# CC1101RGPR.net
KiCad netlist of a schematic drawn in Altium Designer
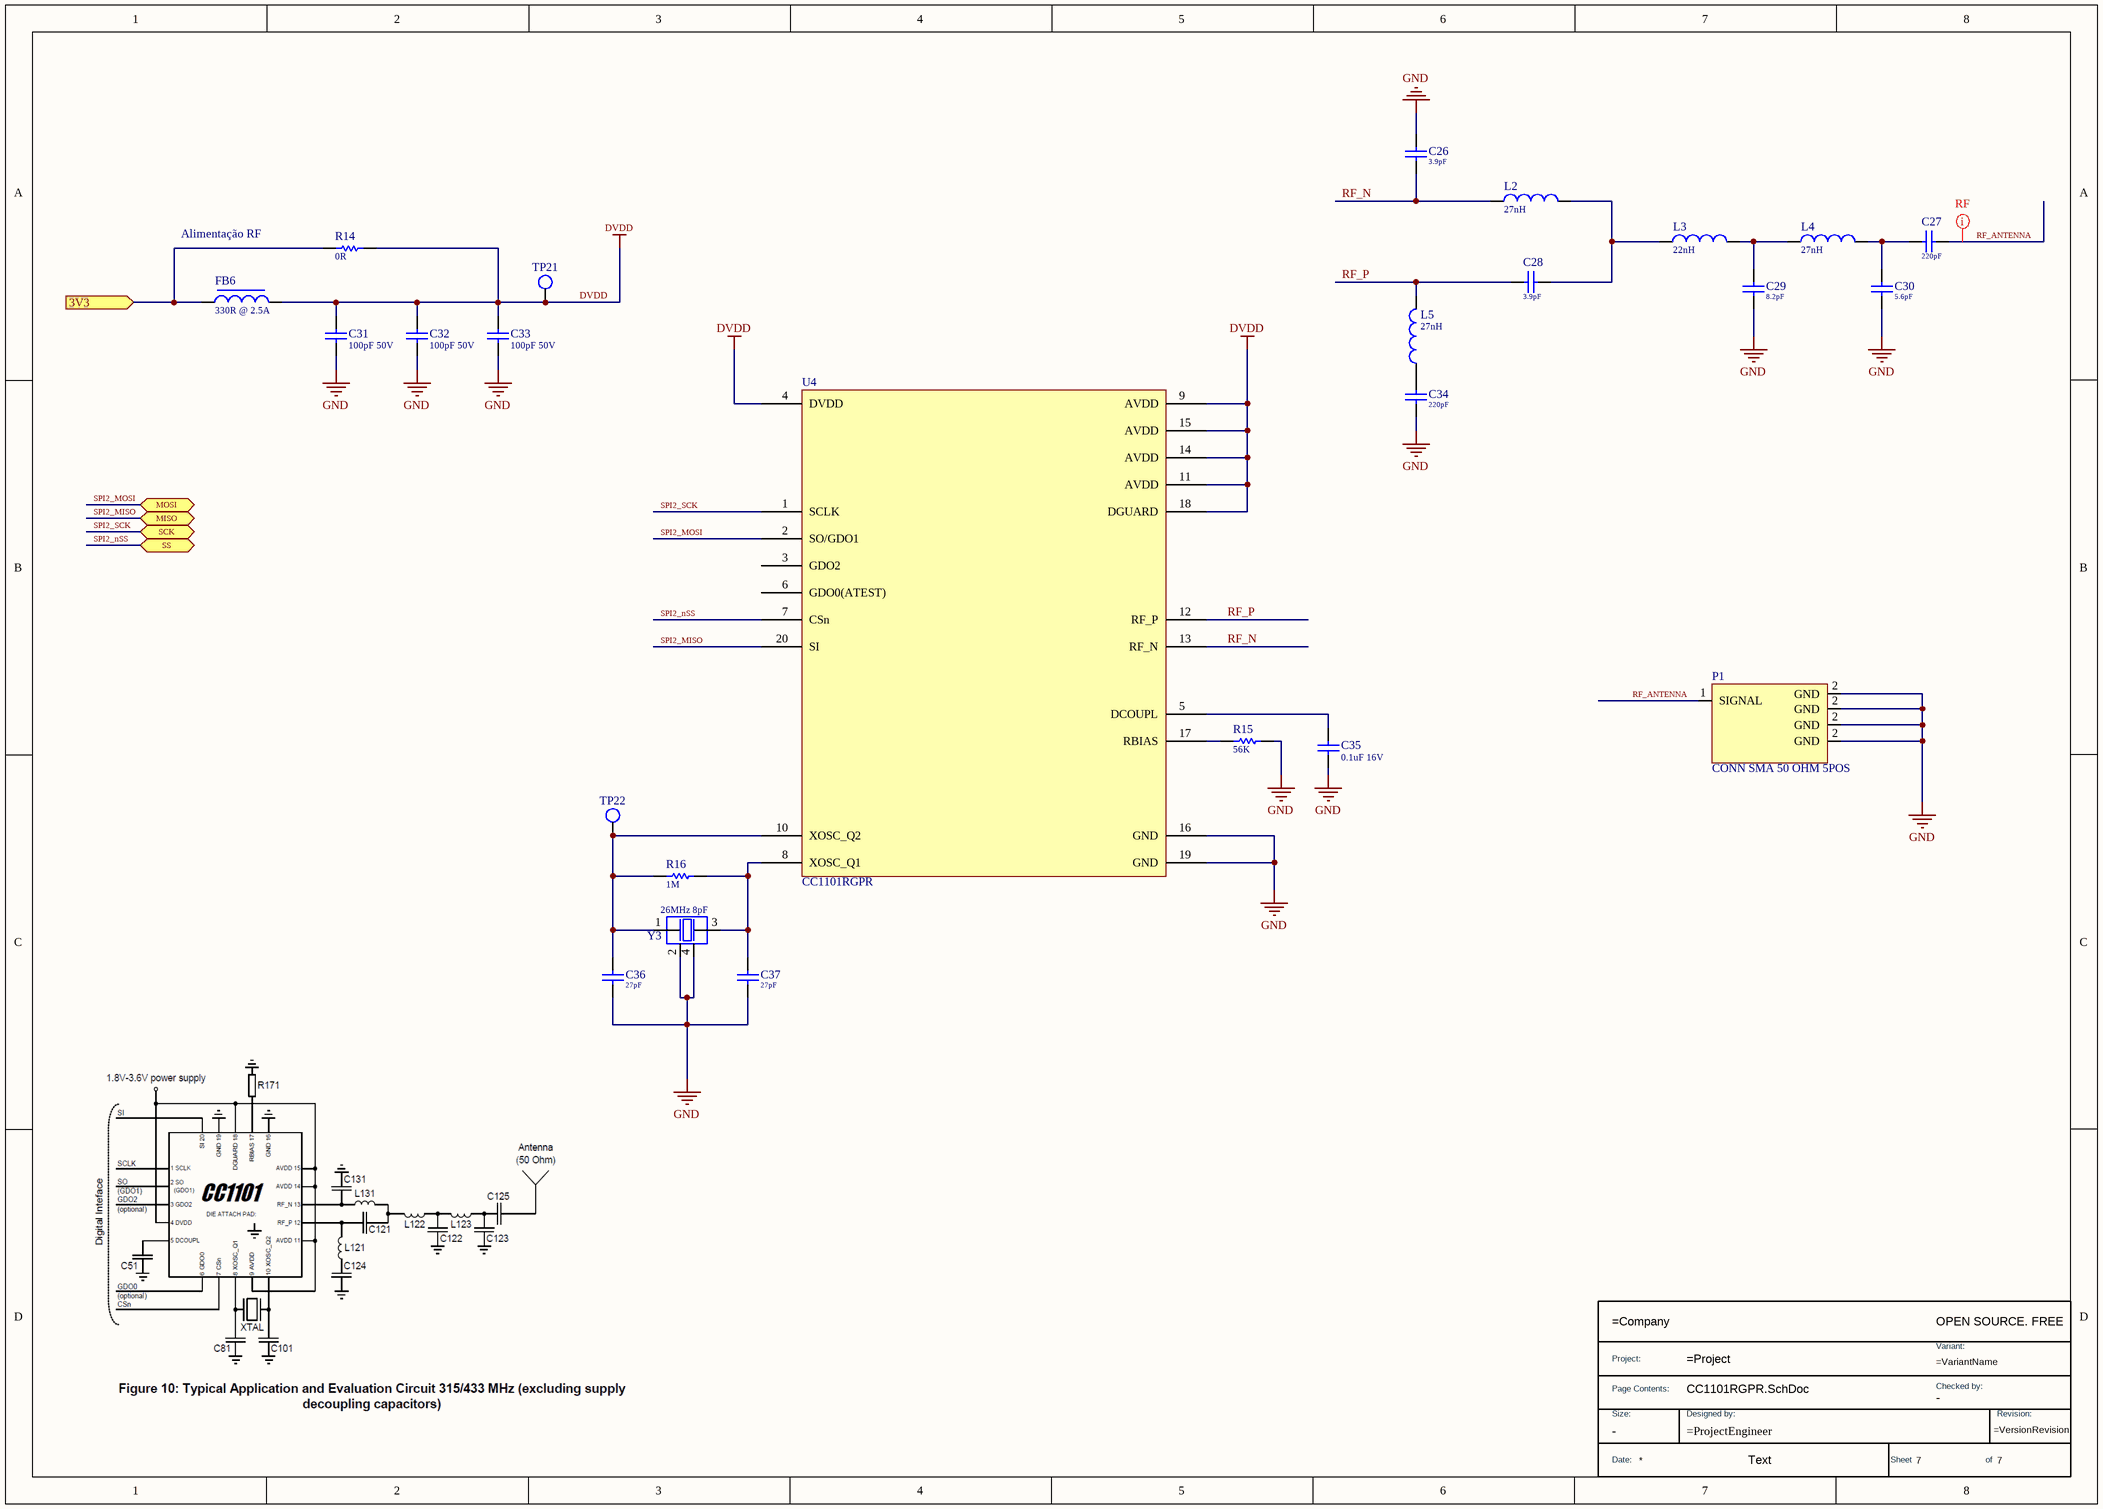
[diagram p0: CC1101RGPR.SchDoc]

(export (version "E")
  (design (tool "Eeschema 10.0.6"))
  (components
    (comp (ref "C26")
      (value "GJM1555C1H3R9WB01D")
      (footprint "CAP 0402")
      (description "CAP CER 3.9PF 50V C0G/NP0 0402")
      (fields (field (name "MANUFACTURER") "Murata Electronics") (field (name "VALOR") "3.9pF"))
      (libsource (lib "OBDH_Ed02") (part "GJM1555C1H3R9WB01D"))
    )
    (comp (ref "C27")
      (value "GRM155R71H221JA01D")
      (footprint "CAP 0402")
      (description "CAP CER 220PF 50V X7R 0402")
      (fields (field (name "MANUFACTURER") "Murata Electronics") (field (name "VALOR") "220pF"))
      (libsource (lib "OBDH_Ed02") (part "GRM155R71H221JA01D"))
    )
    (comp (ref "C28")
      (value "GJM1555C1H3R9WB01D")
      (footprint "CAP 0402")
      (description "CAP CER 3.9PF 50V C0G/NP0 0402")
      (fields (field (name "MANUFACTURER") "Murata Electronics") (field (name "VALOR") "3.9pF"))
      (libsource (lib "OBDH_Ed02") (part "GJM1555C1H3R9WB01D"))
    )
    (comp (ref "C29")
      (value "GCM1555C1H8R2CA16D")
      (footprint "CAP 0402")
      (description "CAP CER 8.2PF 50V C0G/NP0 0402")
      (fields (field (name "MANUFACTURER") "Murata Electronics") (field (name "VALOR") "8.2pF"))
      (libsource (lib "OBDH_Ed02") (part "GCM1555C1H8R2CA16D"))
    )
    (comp (ref "C30")
      (value "GRM1555C1H5R6CA01D")
      (footprint "CAP 0402")
      (description "CAP CER 5.6PF 50V C0G/NP0 0402")
      (fields (field (name "MANUFACTURER") "Murata Electronics") (field (name "VALOR") "5.6pF"))
      (libsource (lib "OBDH_Ed02") (part "GRM1555C1H5R6CA01D"))
    )
    (comp (ref "C31")
      (value "CC0805JRNPO9BN101")
      (footprint "CAP_0805")
      (description "CAP CER 100PF 50V C0G/NPO 0805")
      (fields (field (name "MANUFACTURER") "YAGEO") (field (name "VALOR") "100pF 50V"))
      (libsource (lib "OBDH_Ed02") (part "CC0805JRNPO9BN101"))
    )
    (comp (ref "C32")
      (value "CC0805JRNPO9BN101")
      (footprint "CAP_0805")
      (description "CAP CER 100PF 50V C0G/NPO 0805")
      (fields (field (name "MANUFACTURER") "YAGEO") (field (name "VALOR") "100pF 50V"))
      (libsource (lib "OBDH_Ed02") (part "CC0805JRNPO9BN101"))
    )
    (comp (ref "C33")
      (value "CC0805JRNPO9BN101")
      (footprint "CAP_0805")
      (description "CAP CER 100PF 50V C0G/NPO 0805")
      (fields (field (name "MANUFACTURER") "YAGEO") (field (name "VALOR") "100pF 50V"))
      (libsource (lib "OBDH_Ed02") (part "CC0805JRNPO9BN101"))
    )
    (comp (ref "C34")
      (value "GRM155R71H221JA01D")
      (footprint "CAP 0402")
      (description "CAP CER 220PF 50V X7R 0402")
      (fields (field (name "MANUFACTURER") "Murata Electronics") (field (name "VALOR") "220pF"))
      (libsource (lib "OBDH_Ed02") (part "GRM155R71H221JA01D"))
    )
    (comp (ref "C35")
      (value "CL05B104KO5NNNC")
      (footprint "CAP_0805")
      (description "CAP CER 0.1UF 16V X5R 0805")
      (fields (field (name "MANUFACTURER") "Samsung Electro-Mechanics") (field (name "VALOR") "0.1uF 16V"))
      (libsource (lib "OBDH_Ed02") (part "CL05B104KO5NNNC"))
    )
    (comp (ref "C36")
      (value "GCM1555C1H270JA16D")
      (footprint "CAP 0402")
      (description "CAP CER 27PF 50V C0G/NP0 0402")
      (fields (field (name "MANUFACTURER") "Murata Electronics") (field (name "VALOR") "27pF"))
      (libsource (lib "OBDH_Ed02") (part "GCM1555C1H270JA16D"))
    )
    (comp (ref "C37")
      (value "GCM1555C1H270JA16D")
      (footprint "CAP 0402")
      (description "CAP CER 27PF 50V C0G/NP0 0402")
      (fields (field (name "MANUFACTURER") "Murata Electronics") (field (name "VALOR") "27pF"))
      (libsource (lib "OBDH_Ed02") (part "GCM1555C1H270JA16D"))
    )
    (comp (ref "FB6")
      (value "MPZ2012S331AT000")
      (footprint "IND_0805")
      (description "FERRITE BEAD 330 OHM 0805 1LN")
      (fields (field (name "MANUFACTURER") "TDK Corporation") (field (name "VALOR") "330R @ 2.5A"))
      (libsource (lib "OBDH_Ed02") (part "MPZ2012S331AT000"))
    )
    (comp (ref "L2")
      (value "27nH")
      (footprint "IND 0402")
      (description "FIXED IND 27NH 350MA 460MOHM SMD")
      (fields
        (field (name "MANUFACTURER") "Murata Electronics")
        (field (name "MANUFACTURER PART NUMBER") "LQG15HS27NH02D")
      )
      (libsource (lib "OBDH_Ed02") (part "LQG15HS27NH02D"))
    )
    (comp (ref "L3")
      (value "22nH")
      (footprint "IND 0402")
      (description "FIXED IND 22NH 350MA 580MOHM SMD")
      (fields
        (field (name "MANUFACTURER") "Murata Electronics")
        (field (name "MANUFACTURER PART NUMBER") "LQG15HN22NH02D")
      )
      (libsource (lib "OBDH_Ed02") (part "LQG15HN22NH02D"))
    )
    (comp (ref "L4")
      (value "27nH")
      (footprint "IND 0402")
      (description "FIXED IND 27NH 350MA 460MOHM SMD")
      (fields
        (field (name "MANUFACTURER") "Murata Electronics")
        (field (name "MANUFACTURER PART NUMBER") "LQG15HS27NH02D")
      )
      (libsource (lib "OBDH_Ed02") (part "LQG15HS27NH02D"))
    )
    (comp (ref "L5")
      (value "27nH")
      (footprint "IND 0402")
      (description "FIXED IND 27NH 350MA 460MOHM SMD")
      (fields
        (field (name "MANUFACTURER") "Murata Electronics")
        (field (name "MANUFACTURER PART NUMBER") "LQG15HS27NH02D")
      )
      (libsource (lib "OBDH_Ed02") (part "LQG15HS27NH02D"))
    )
    (comp (ref "P1")
      (value "CONN SMA 50 OHM 5POS")
      (footprint "CONN PTH SMA JACK CONSMA002-L-G")
      (description "CONN SMA JACK R/A 50OHM PCB")
      (libsource (lib "OBDH_Ed02") (part "CONN SMA 50 OHM 5POS"))
    )
    (comp (ref "R14")
      (value "RC0805JR-070RL")
      (footprint "RES_0805")
      (description "RES 0 OHM JUMPER 1/8W 0805")
      (fields (field (name "MANUFACTURER") "YAGEO") (field (name "VALOR") "0R"))
      (libsource (lib "OBDH_Ed02") (part "RC0805JR-070RL"))
    )
    (comp (ref "R15")
      (value "**CRCW080562K0JNEA")
      (footprint "RES_0805")
      (description "RES SMD 56K OHM 5% 1/8W 0805")
      (fields
        (field (name "MANUFACTURER") "YAGEO")
        (field (name "MANUFACTURER PART NUMBER") "CRCW080562K0JNEA")
        (field (name "VALOR") "56K")
      )
      (libsource (lib "OBDH_Ed02") (part "**CRCW080562K0JNEA"))
    )
    (comp (ref "R16")
      (value "CRCW08051M00JNEA")
      (footprint "RES 0402")
      (description "RES SMD 1M OHM 5% 1/8W 0805")
      (fields (field (name "MANUFACTURER") "Vishay Intertech") (field (name "VALOR") "1M"))
      (libsource (lib "OBDH_Ed02") (part "CRCW08051M00JNEA"))
    )
    (comp (ref "TP21")
      (value "TEST_POINT_1.5MM")
      (footprint "TESTPOINT_1.5MM")
      (description "TEST_POINT")
      (libsource (lib "OBDH_Ed02") (part "TEST_POINT_1.5MM"))
    )
    (comp (ref "TP22")
      (value "TEST_POINT_1.5MM")
      (footprint "TESTPOINT_1.5MM")
      (description "TEST_POINT")
      (libsource (lib "OBDH_Ed02") (part "TEST_POINT_1.5MM"))
    )
    (comp (ref "U4")
      (value "CC1101RGPR")
      (footprint "QLP-4x4")
      (description "IC RF TXRX ISM<1GHZ 20VFQFN")
      (libsource (lib "OBDH_Ed02") (part "CC1101RGPR"))
    )
    (comp (ref "Y3")
      (value "NX3225SA-26MHZ")
      (footprint "Crystal-4SMD")
      (description "CRYSTAL 26.0000MHZ 10PF SMD")
      (fields (field (name "MANUFACTURER") "NDK America, Inc.") (field (name "VALOR") "26MHz 8pF"))
      (libsource (lib "OBDH_Ed02") (part "NX3225SA-26MHZ"))
    )
  )
  (nets
    (net (code "1") (name "/3V3") (class "Default")
      (node (ref "FB6") (pin "1") (pinfunction "1_1") (pintype "passive"))
      (node (ref "R14") (pin "1") (pinfunction "1_1") (pintype "passive"))
    )
    (net (code "2") (name "/RF_ANTENNA") (class "Default")
      (node (ref "C27") (pin "2") (pinfunction "2_2") (pintype "passive"))
      (node (ref "P1") (pin "1") (pinfunction "SIGNAL_1") (pintype "passive"))
    )
    (net (code "3") (name "/RF_N") (class "Default")
      (node (ref "C26") (pin "1") (pinfunction "1_1") (pintype "passive"))
      (node (ref "L2") (pin "1") (pinfunction "1_1") (pintype "passive"))
      (node (ref "U4") (pin "13") (pinfunction "RF_N_13") (pintype "passive"))
    )
    (net (code "4") (name "/RF_P") (class "Default")
      (node (ref "C28") (pin "1") (pinfunction "1_1") (pintype "passive"))
      (node (ref "L5") (pin "2") (pinfunction "2_2") (pintype "passive"))
      (node (ref "U4") (pin "12") (pinfunction "RF_P_12") (pintype "passive"))
    )
    (net (code "5") (name "/SPI2_MISO") (class "Default")
      (node (ref "U4") (pin "20") (pinfunction "SI_20") (pintype "passive"))
    )
    (net (code "6") (name "/SPI2_MOSI") (class "Default")
      (node (ref "U4") (pin "2") (pinfunction "SO/GDO1_2") (pintype "passive"))
    )
    (net (code "7") (name "/SPI2_SCK") (class "Default")
      (node (ref "U4") (pin "1") (pinfunction "SCLK_1") (pintype "passive"))
    )
    (net (code "8") (name "/SPI2_nSS") (class "Default")
      (node (ref "U4") (pin "7") (pinfunction "CSn_7") (pintype "passive"))
    )
    (net (code "9") (name "DVDD") (class "Default")
      (node (ref "C31") (pin "2") (pinfunction "2_2") (pintype "passive"))
      (node (ref "C32") (pin "2") (pinfunction "2_2") (pintype "passive"))
      (node (ref "C33") (pin "2") (pinfunction "2_2") (pintype "passive"))
      (node (ref "FB6") (pin "2") (pinfunction "2_2") (pintype "passive"))
      (node (ref "R14") (pin "2") (pinfunction "2_2") (pintype "passive"))
      (node (ref "TP21") (pin "1") (pinfunction "1_1") (pintype "passive"))
      (node (ref "U4") (pin "11") (pinfunction "AVDD_11") (pintype "passive"))
      (node (ref "U4") (pin "14") (pinfunction "AVDD_14") (pintype "passive"))
      (node (ref "U4") (pin "15") (pinfunction "AVDD_15") (pintype "passive"))
      (node (ref "U4") (pin "18") (pinfunction "DGUARD_18") (pintype "passive"))
      (node (ref "U4") (pin "4") (pinfunction "DVDD_4") (pintype "passive"))
      (node (ref "U4") (pin "9") (pinfunction "AVDD_9") (pintype "passive"))
    )
    (net (code "10") (name "GND") (class "Default")
      (node (ref "C26") (pin "2") (pinfunction "2_2") (pintype "passive"))
      (node (ref "C29") (pin "2") (pinfunction "2_2") (pintype "passive"))
      (node (ref "C30") (pin "1") (pinfunction "1_1") (pintype "passive"))
      (node (ref "C31") (pin "1") (pinfunction "1_1") (pintype "passive"))
      (node (ref "C32") (pin "1") (pinfunction "1_1") (pintype "passive"))
      (node (ref "C33") (pin "1") (pinfunction "1_1") (pintype "passive"))
      (node (ref "C34") (pin "1") (pinfunction "1_1") (pintype "passive"))
      (node (ref "C35") (pin "1") (pinfunction "1_1") (pintype "passive"))
      (node (ref "C36") (pin "1") (pinfunction "1_1") (pintype "passive"))
      (node (ref "C37") (pin "1") (pinfunction "1_1") (pintype "passive"))
      (node (ref "P1") (pin "2") (pinfunction "GND_2") (pintype "power_in"))
      (node (ref "R15") (pin "2") (pinfunction "2_2") (pintype "passive"))
      (node (ref "U4") (pin "16") (pinfunction "GND_16") (pintype "passive"))
      (node (ref "U4") (pin "19") (pinfunction "GND_19") (pintype "passive"))
      (node (ref "Y3") (pin "2") (pinfunction "2_2") (pintype "passive"))
      (node (ref "Y3") (pin "4") (pinfunction "4_4") (pintype "passive"))
    )
    (net (code "11") (name "Net-(C27-Pad1)") (class "Default")
      (node (ref "C27") (pin "1") (pinfunction "1_1") (pintype "passive"))
      (node (ref "C30") (pin "2") (pinfunction "2_2") (pintype "passive"))
      (node (ref "L4") (pin "2") (pinfunction "2_2") (pintype "passive"))
    )
    (net (code "12") (name "Net-(C28-Pad2)") (class "Default")
      (node (ref "C28") (pin "2") (pinfunction "2_2") (pintype "passive"))
      (node (ref "L2") (pin "2") (pinfunction "2_2") (pintype "passive"))
      (node (ref "L3") (pin "1") (pinfunction "1_1") (pintype "passive"))
    )
    (net (code "13") (name "Net-(C29-Pad1)") (class "Default")
      (node (ref "C29") (pin "1") (pinfunction "1_1") (pintype "passive"))
      (node (ref "L3") (pin "2") (pinfunction "2_2") (pintype "passive"))
      (node (ref "L4") (pin "1") (pinfunction "1_1") (pintype "passive"))
    )
    (net (code "14") (name "Net-(C34-Pad2)") (class "Default")
      (node (ref "C34") (pin "2") (pinfunction "2_2") (pintype "passive"))
      (node (ref "L5") (pin "1") (pinfunction "1_1") (pintype "passive"))
    )
    (net (code "15") (name "Net-(U4-DCOUPL)") (class "Default")
      (node (ref "C35") (pin "2") (pinfunction "2_2") (pintype "passive"))
      (node (ref "U4") (pin "5") (pinfunction "DCOUPL_5") (pintype "passive"))
    )
    (net (code "16") (name "Net-(U4-RBIAS)") (class "Default")
      (node (ref "R15") (pin "1") (pinfunction "1_1") (pintype "passive"))
      (node (ref "U4") (pin "17") (pinfunction "RBIAS_17") (pintype "passive"))
    )
    (net (code "17") (name "Net-(U4-XOSC_Q1)") (class "Default")
      (node (ref "C37") (pin "2") (pinfunction "2_2") (pintype "passive"))
      (node (ref "R16") (pin "2") (pinfunction "2_2") (pintype "passive"))
      (node (ref "U4") (pin "8") (pinfunction "XOSC_Q1_8") (pintype "passive"))
      (node (ref "Y3") (pin "3") (pinfunction "3_3") (pintype "passive"))
    )
    (net (code "18") (name "Net-(U4-XOSC_Q2)") (class "Default")
      (node (ref "C36") (pin "2") (pinfunction "2_2") (pintype "passive"))
      (node (ref "R16") (pin "1") (pinfunction "1_1") (pintype "passive"))
      (node (ref "TP22") (pin "1") (pinfunction "1_1") (pintype "passive"))
      (node (ref "U4") (pin "10") (pinfunction "XOSC_Q2_10") (pintype "passive"))
      (node (ref "Y3") (pin "1") (pinfunction "1_1") (pintype "passive"))
    )
    (net (code "19") (name "unconnected-(U4-GDO0(ATEST)-Pad6)") (class "Default")
      (node (ref "U4") (pin "6") (pinfunction "GDO0(ATEST)_6") (pintype "passive"))
    )
    (net (code "20") (name "unconnected-(U4-GDO2-Pad3)") (class "Default")
      (node (ref "U4") (pin "3") (pinfunction "GDO2_3") (pintype "passive"))
    )
  )
)
